# uartjtag_block.net
KiCad netlist of a schematic drawn in Altium Designer
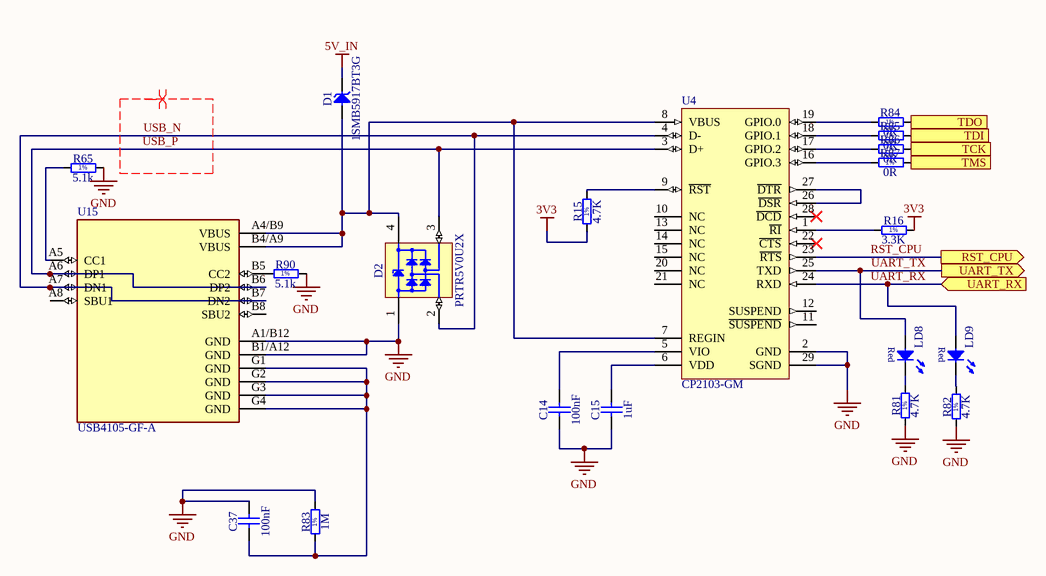
[diagram p0: uartjtag_block.SchDoc]

(export (version "E")
  (design (tool "Eeschema 10.0.6"))
  (components
    (comp (ref "C14")
      (value "100nF")
      (footprint "CAPC2013X100N")
      (description "Non-polarised capacitor")
      (fields
        (field (name "PART NUMBER") "CC0805_1.5NF_50V_5%_C0G")
        (field (name "VOLTAGE") "50V")
        (field (name "AUTHOR") "CERN DEM BC")
      )
      (libsource (lib "Capacitors") (part "Capacitor - non polarized"))
    )
    (comp (ref "C15")
      (value "1uF")
      (footprint "CAPC2013X100N")
      (description "Non-polarised capacitor")
      (fields
        (field (name "PART NUMBER") "CC0805_1.5NF_50V_5%_C0G")
        (field (name "VOLTAGE") "50V")
        (field (name "AUTHOR") "CERN DEM BC")
      )
      (libsource (lib "Capacitors") (part "Capacitor - non polarized"))
    )
    (comp (ref "C37")
      (value "100nF")
      (footprint "CAPC2013X100N")
      (description "Non-polarised capacitor")
      (fields
        (field (name "PART NUMBER") "CC0805_1.5NF_50V_5%_C0G")
        (field (name "VOLTAGE") "50V")
        (field (name "AUTHOR") "CERN DEM BC")
      )
      (libsource (lib "Capacitors") (part "Capacitor - non polarized"))
    )
    (comp (ref "D1")
      (value "1SMB5917BT3G")
      (footprint "DIOM5436X244N")
      (description "Zener Diode")
      (fields
        (field (name "VOLTAGE") "4.7V")
        (field (name "POWER") "3W")
        (field (name "AUTHOR") "CERN DEM MR")
      )
      (libsource (lib "ICs And Semiconductors") (part "Diode Zener"))
    )
    (comp (ref "D2")
      (value "PRTR5V0U2X")
      (footprint "SOT190P230X110-4N")
      (description "Ultra Low Capacitance Double Rail-to-Rail ESD Protection Diode")
      (fields
        (field (name "VOLTAGE") "5.5V")
        (field (name "MANUFACTURER") "NXP SEMICONDUCTORS")
        (field (name "AUTHOR") "CERN DEM JLC")
      )
      (libsource (lib "ICs And Semiconductors") (part "PRTR5V0U2X"))
    )
    (comp (ref "LD8")
      (value "Super Red")
      (footprint "LED_OSRAM_LSR976")
      (description "LED Red 1C 2A")
      (fields
        (field (name "PART NUMBER") "LED_OSRAM_LSR976")
        (field (name "MANUFACTURER") "OSRAM")
        (field (name "AUTHOR") "CERN DEM JLC")
      )
      (libsource (lib "ICs And Semiconductors") (part "LED Red 1C 2A"))
    )
    (comp (ref "LD9")
      (value "Super Red")
      (footprint "LED_OSRAM_LSR976")
      (description "LED Red 1C 2A")
      (fields
        (field (name "PART NUMBER") "LED_OSRAM_LSR976")
        (field (name "MANUFACTURER") "OSRAM")
        (field (name "AUTHOR") "CERN DEM JLC")
      )
      (libsource (lib "ICs And Semiconductors") (part "LED Red 1C 2A"))
    )
    (comp (ref "R15")
      (value "4.7K")
      (footprint "RESC1608X55N")
      (description "Resistor - 1%")
      (fields
        (field (name "PART NUMBER") "R0603_100K_1%_0.1W_100PPM")
        (field (name "POWER") "0.1W")
        (field (name "AUTHOR") "CERN DEM JLC")
      )
      (libsource (lib "Resistors") (part "Resistor - 1%"))
    )
    (comp (ref "R16")
      (value "3.3K")
      (footprint "RESC1608X55N")
      (description "Resistor - 1%")
      (fields
        (field (name "PART NUMBER") "R0603_100K_1%_0.1W_100PPM")
        (field (name "POWER") "0.1W")
        (field (name "AUTHOR") "CERN DEM JLC")
      )
      (libsource (lib "Resistors") (part "Resistor - 1%"))
    )
    (comp (ref "R65")
      (value "5.1k")
      (footprint "RESC1608X55N")
      (description "Resistor - 1%")
      (fields
        (field (name "PART NUMBER") "R0603_100K_1%_0.1W_100PPM")
        (field (name "POWER") "0.1W")
        (field (name "AUTHOR") "CERN DEM JLC")
      )
      (libsource (lib "Resistors") (part "Resistor - 1%"))
    )
    (comp (ref "R81")
      (value "4.7K")
      (footprint "RESC1608X55N")
      (description "Resistor - 1%")
      (fields
        (field (name "PART NUMBER") "R0603_100K_1%_0.1W_100PPM")
        (field (name "POWER") "0.1W")
        (field (name "AUTHOR") "CERN DEM JLC")
      )
      (libsource (lib "Resistors") (part "Resistor - 1%"))
    )
    (comp (ref "R82")
      (value "4.7K")
      (footprint "RESC1608X55N")
      (description "Resistor - 1%")
      (fields
        (field (name "PART NUMBER") "R0603_100K_1%_0.1W_100PPM")
        (field (name "POWER") "0.1W")
        (field (name "AUTHOR") "CERN DEM JLC")
      )
      (libsource (lib "Resistors") (part "Resistor - 1%"))
    )
    (comp (ref "R83")
      (value "1M")
      (footprint "RESC1608X55N")
      (description "Resistor - 1%")
      (fields
        (field (name "PART NUMBER") "R0603_100K_1%_0.1W_100PPM")
        (field (name "POWER") "0.1W")
        (field (name "AUTHOR") "CERN DEM JLC")
      )
      (libsource (lib "Resistors") (part "Resistor - 1%"))
    )
    (comp (ref "R84")
      (value "0R")
      (footprint "RESC1608X55N")
      (description "Resistor - 1%")
      (fields
        (field (name "PART NUMBER") "R0603_100K_1%_0.1W_100PPM")
        (field (name "POWER") "0.1W")
        (field (name "AUTHOR") "CERN DEM JLC")
      )
      (libsource (lib "Resistors") (part "Resistor - 1%"))
    )
    (comp (ref "R85")
      (value "0R")
      (footprint "RESC1608X55N")
      (description "Resistor - 1%")
      (fields
        (field (name "PART NUMBER") "R0603_100K_1%_0.1W_100PPM")
        (field (name "POWER") "0.1W")
        (field (name "AUTHOR") "CERN DEM JLC")
      )
      (libsource (lib "Resistors") (part "Resistor - 1%"))
    )
    (comp (ref "R86")
      (value "0R")
      (footprint "RESC1608X55N")
      (description "Resistor - 1%")
      (fields
        (field (name "PART NUMBER") "R0603_100K_1%_0.1W_100PPM")
        (field (name "POWER") "0.1W")
        (field (name "AUTHOR") "CERN DEM JLC")
      )
      (libsource (lib "Resistors") (part "Resistor - 1%"))
    )
    (comp (ref "R87")
      (value "0R")
      (footprint "RESC1608X55N")
      (description "Resistor - 1%")
      (fields
        (field (name "PART NUMBER") "R0603_100K_1%_0.1W_100PPM")
        (field (name "POWER") "0.1W")
        (field (name "AUTHOR") "CERN DEM JLC")
      )
      (libsource (lib "Resistors") (part "Resistor - 1%"))
    )
    (comp (ref "R90")
      (value "5.1k")
      (footprint "RESC1608X55N")
      (description "Resistor - 1%")
      (fields
        (field (name "PART NUMBER") "R0603_100K_1%_0.1W_100PPM")
        (field (name "POWER") "0.1W")
        (field (name "AUTHOR") "CERN DEM JLC")
      )
      (libsource (lib "Resistors") (part "Resistor - 1%"))
    )
    (comp (ref "U4")
      (value "CP2103-GM")
      (footprint "SLAB-QFN-28-3125x3125TP_A_L")
      (description "Single-Chip USB to UART Bridge, 1024 Bytes EEPROM, -40 to 85 degC, 28-pin QFN, Tube")
      (fields (field (name "MANUFACTURER") "Silicon Labs"))
      (libsource (lib "Silicon Labs Interface") (part "CP2103-GM"))
    )
    (comp (ref "U15")
      (value "USB4105-GF-A")
      (footprint "GCT_USB4105-GF-A")
      (fields (field (name "MF") "GCT"))
      (libsource (lib "SnapEDAsch") (part "USB4105-GF-A"))
    )
  )
  (nets
    (net (code "1") (name "/RST_CPU") (class "Default")
      (node (ref "U4") (pin "23") (pinfunction "~{RTS}_23") (pintype "output"))
    )
    (net (code "2") (name "/TCK") (class "Default")
      (node (ref "R86") (pin "2") (pinfunction "2_2") (pintype "passive"))
    )
    (net (code "3") (name "/TDI") (class "Default")
      (node (ref "R85") (pin "2") (pinfunction "2_2") (pintype "passive"))
    )
    (net (code "4") (name "/TDO") (class "Default")
      (node (ref "R84") (pin "2") (pinfunction "2_2") (pintype "passive"))
    )
    (net (code "5") (name "/TMS") (class "Default")
      (node (ref "R87") (pin "2") (pinfunction "2_2") (pintype "passive"))
    )
    (net (code "6") (name "/UART_RX") (class "Default")
      (node (ref "LD9") (pin "2") (pinfunction "A_2") (pintype "passive"))
      (node (ref "U4") (pin "24") (pinfunction "RXD_24") (pintype "input"))
    )
    (net (code "7") (name "/UART_TX") (class "Default")
      (node (ref "LD8") (pin "2") (pinfunction "A_2") (pintype "passive"))
      (node (ref "U4") (pin "25") (pinfunction "TXD_25") (pintype "output"))
    )
    (net (code "8") (name "/USB_N") (class "Default")
      (node (ref "D2") (pin "2") (pinfunction "I/O1_2") (pintype "bidirectional"))
      (node (ref "U15") (pin "A7") (pinfunction "DN1_A7") (pintype "bidirectional"))
      (node (ref "U15") (pin "B7") (pinfunction "DN2_B7") (pintype "bidirectional"))
      (node (ref "U4") (pin "4") (pinfunction "D-_4") (pintype "bidirectional"))
    )
    (net (code "9") (name "/USB_P") (class "Default")
      (node (ref "D2") (pin "3") (pinfunction "I/O2_3") (pintype "bidirectional"))
      (node (ref "U15") (pin "A6") (pinfunction "DP1_A6") (pintype "bidirectional"))
      (node (ref "U15") (pin "B6") (pinfunction "DP2_B6") (pintype "bidirectional"))
      (node (ref "U4") (pin "3") (pinfunction "D+_3") (pintype "bidirectional"))
    )
    (net (code "10") (name "3V3") (class "Default")
      (node (ref "R15") (pin "1") (pinfunction "1_1") (pintype "passive"))
      (node (ref "R16") (pin "2") (pinfunction "2_2") (pintype "passive"))
    )
    (net (code "11") (name "5V_IN") (class "Default")
      (node (ref "D1") (pin "1") (pinfunction "C_1") (pintype "passive"))
    )
    (net (code "12") (name "GND") (class "Default")
      (node (ref "C14") (pin "1") (pinfunction "1_1") (pintype "passive"))
      (node (ref "C15") (pin "1") (pinfunction "1_1") (pintype "passive"))
      (node (ref "C37") (pin "2") (pinfunction "2_2") (pintype "passive"))
      (node (ref "D2") (pin "1") (pinfunction "GND_1") (pintype "power_in"))
      (node (ref "R65") (pin "2") (pinfunction "2_2") (pintype "passive"))
      (node (ref "R81") (pin "1") (pinfunction "1_1") (pintype "passive"))
      (node (ref "R82") (pin "1") (pinfunction "1_1") (pintype "passive"))
      (node (ref "R83") (pin "2") (pinfunction "2_2") (pintype "passive"))
      (node (ref "R90") (pin "2") (pinfunction "2_2") (pintype "passive"))
      (node (ref "U15") (pin "A1/B12") (pinfunction "GND_A1/B12") (pintype "power_in"))
      (node (ref "U15") (pin "B1/A12") (pinfunction "GND_B1/A12") (pintype "power_in"))
      (node (ref "U4") (pin "2") (pinfunction "GND_2") (pintype "power_in"))
      (node (ref "U4") (pin "29") (pinfunction "SGND_29") (pintype "power_in"))
    )
    (net (code "13") (name "Net-(C37-Pad1)") (class "Default")
      (node (ref "C37") (pin "1") (pinfunction "1_1") (pintype "passive"))
      (node (ref "R83") (pin "1") (pinfunction "1_1") (pintype "passive"))
      (node (ref "U15") (pin "G1") (pinfunction "GND_G1") (pintype "power_in"))
      (node (ref "U15") (pin "G2") (pinfunction "GND_G2") (pintype "power_in"))
      (node (ref "U15") (pin "G3") (pinfunction "GND_G3") (pintype "power_in"))
      (node (ref "U15") (pin "G4") (pinfunction "GND_G4") (pintype "power_in"))
    )
    (net (code "14") (name "Net-(D1-A)") (class "Default")
      (node (ref "D1") (pin "2") (pinfunction "A_2") (pintype "passive"))
      (node (ref "D2") (pin "4") (pinfunction "VCC_4") (pintype "power_in"))
      (node (ref "U15") (pin "A4/B9") (pinfunction "VBUS_A4/B9") (pintype "power_in"))
      (node (ref "U15") (pin "B4/A9") (pinfunction "VBUS_B4/A9") (pintype "power_in"))
      (node (ref "U4") (pin "7") (pinfunction "REGIN_7") (pintype "power_in"))
      (node (ref "U4") (pin "8") (pinfunction "VBUS_8") (pintype "input"))
    )
    (net (code "15") (name "Net-(LD8-C)") (class "Default")
      (node (ref "LD8") (pin "1") (pinfunction "C_1") (pintype "passive"))
      (node (ref "R81") (pin "2") (pinfunction "2_2") (pintype "passive"))
    )
    (net (code "16") (name "Net-(LD9-C)") (class "Default")
      (node (ref "LD9") (pin "1") (pinfunction "C_1") (pintype "passive"))
      (node (ref "R82") (pin "2") (pinfunction "2_2") (pintype "passive"))
    )
    (net (code "17") (name "Net-(U4-GPIO.0)") (class "Default")
      (node (ref "R84") (pin "1") (pinfunction "1_1") (pintype "passive"))
      (node (ref "U4") (pin "19") (pinfunction "GPIO.0_19") (pintype "bidirectional"))
    )
    (net (code "18") (name "Net-(U4-GPIO.1)") (class "Default")
      (node (ref "R85") (pin "1") (pinfunction "1_1") (pintype "passive"))
      (node (ref "U4") (pin "18") (pinfunction "GPIO.1_18") (pintype "bidirectional"))
    )
    (net (code "19") (name "Net-(U4-GPIO.2)") (class "Default")
      (node (ref "R86") (pin "1") (pinfunction "1_1") (pintype "passive"))
      (node (ref "U4") (pin "17") (pinfunction "GPIO.2_17") (pintype "bidirectional"))
    )
    (net (code "20") (name "Net-(U4-GPIO.3)") (class "Default")
      (node (ref "R87") (pin "1") (pinfunction "1_1") (pintype "passive"))
      (node (ref "U4") (pin "16") (pinfunction "GPIO.3_16") (pintype "bidirectional"))
    )
    (net (code "21") (name "Net-(U4-VDD)") (class "Default")
      (node (ref "C15") (pin "2") (pinfunction "2_2") (pintype "passive"))
      (node (ref "U4") (pin "6") (pinfunction "VDD_6") (pintype "power_in"))
    )
    (net (code "22") (name "Net-(U4-VIO)") (class "Default")
      (node (ref "C14") (pin "2") (pinfunction "2_2") (pintype "passive"))
      (node (ref "U4") (pin "5") (pinfunction "VIO_5") (pintype "power_in"))
    )
    (net (code "23") (name "Net-(U4-~{DSR})") (class "Default")
      (node (ref "U4") (pin "26") (pinfunction "~{DSR}_26") (pintype "input"))
      (node (ref "U4") (pin "27") (pinfunction "~{DTR}_27") (pintype "output"))
    )
    (net (code "24") (name "Net-(U4-~{RI})") (class "Default")
      (node (ref "R16") (pin "1") (pinfunction "1_1") (pintype "passive"))
      (node (ref "U4") (pin "1") (pinfunction "~{RI}_1") (pintype "input"))
    )
    (net (code "25") (name "Net-(U4-~{RST})") (class "Default")
      (node (ref "R15") (pin "2") (pinfunction "2_2") (pintype "passive"))
      (node (ref "U4") (pin "9") (pinfunction "~{RST}_9") (pintype "bidirectional"))
    )
    (net (code "26") (name "Net-(U15-CC1)") (class "Default")
      (node (ref "R65") (pin "1") (pinfunction "1_1") (pintype "passive"))
      (node (ref "U15") (pin "A5") (pinfunction "CC1_A5") (pintype "bidirectional"))
    )
    (net (code "27") (name "Net-(U15-CC2)") (class "Default")
      (node (ref "R90") (pin "1") (pinfunction "1_1") (pintype "passive"))
      (node (ref "U15") (pin "B5") (pinfunction "CC2_B5") (pintype "bidirectional"))
    )
    (net (code "28") (name "unconnected-(U4-NC-Pad10)") (class "Default")
      (node (ref "U4") (pin "10") (pinfunction "NC_10") (pintype "passive"))
    )
    (net (code "29") (name "unconnected-(U4-NC-Pad13)") (class "Default")
      (node (ref "U4") (pin "13") (pinfunction "NC_13") (pintype "passive"))
    )
    (net (code "30") (name "unconnected-(U4-NC-Pad14)") (class "Default")
      (node (ref "U4") (pin "14") (pinfunction "NC_14") (pintype "passive"))
    )
    (net (code "31") (name "unconnected-(U4-NC-Pad15)") (class "Default")
      (node (ref "U4") (pin "15") (pinfunction "NC_15") (pintype "passive"))
    )
    (net (code "32") (name "unconnected-(U4-NC-Pad20)") (class "Default")
      (node (ref "U4") (pin "20") (pinfunction "NC_20") (pintype "passive"))
    )
    (net (code "33") (name "unconnected-(U4-NC-Pad21)") (class "Default")
      (node (ref "U4") (pin "21") (pinfunction "NC_21") (pintype "passive"))
    )
    (net (code "34") (name "unconnected-(U4-SUSPEND-Pad12)") (class "Default")
      (node (ref "U4") (pin "12") (pinfunction "SUSPEND_12") (pintype "output"))
    )
    (net (code "35") (name "unconnected-(U4-~{CTS}-Pad22)") (class "Default")
      (node (ref "U4") (pin "22") (pinfunction "~{CTS}_22") (pintype "input+no_connect"))
    )
    (net (code "36") (name "unconnected-(U4-~{DCD}-Pad28)") (class "Default")
      (node (ref "U4") (pin "28") (pinfunction "~{DCD}_28") (pintype "input+no_connect"))
    )
    (net (code "37") (name "unconnected-(U4-~{SUSPEND}-Pad11)") (class "Default")
      (node (ref "U4") (pin "11") (pinfunction "~{SUSPEND}_11") (pintype "output"))
    )
    (net (code "38") (name "unconnected-(U15-SBU1-PadA8)") (class "Default")
      (node (ref "U15") (pin "A8") (pinfunction "SBU1_A8") (pintype "bidirectional"))
    )
    (net (code "39") (name "unconnected-(U15-SBU2-PadB8)") (class "Default")
      (node (ref "U15") (pin "B8") (pinfunction "SBU2_B8") (pintype "bidirectional"))
    )
  )
)
